# switch_strip.net
KiCad netlist of a schematic drawn in EAGLE
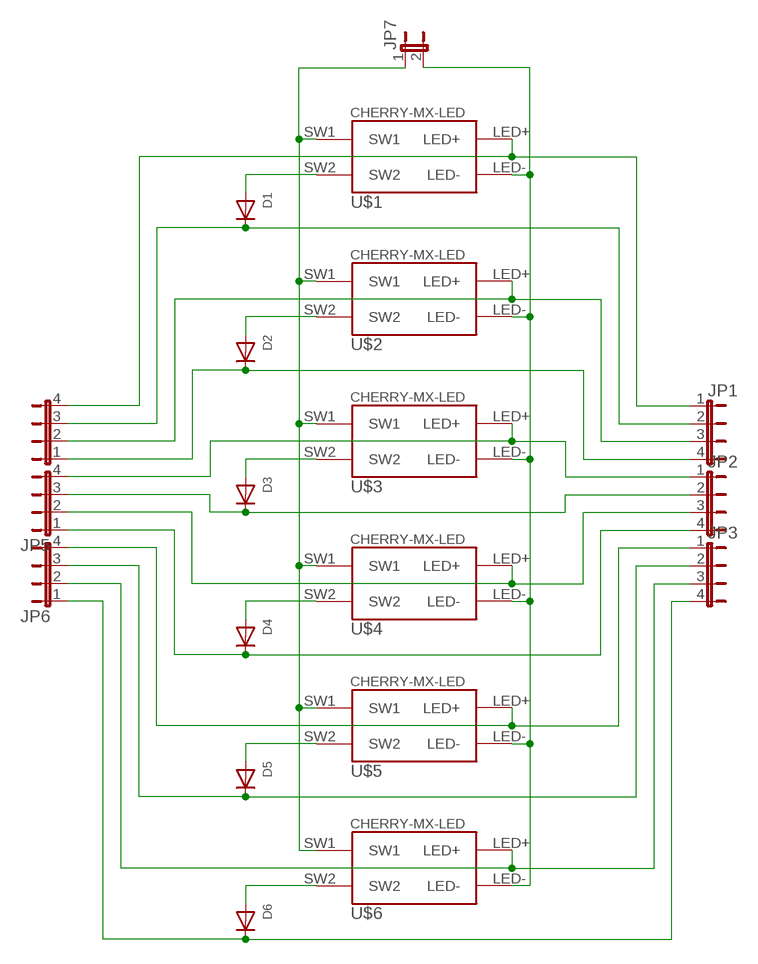
[diagram p0: schematic, sheet 1]

(export (version "E")
  (design (tool "Eeschema 10.0.6"))
  (components
    (comp (ref "D1")
      (value "DIODEDO-1N4148")
      (footprint "eagle-import:DO-1N4148")
      (libsource (lib "eagle-import") (part "DIODEDO-1N4148"))
    )
    (comp (ref "D2")
      (value "DIODEDO-1N4148")
      (footprint "eagle-import:DO-1N4148")
      (libsource (lib "eagle-import") (part "DIODEDO-1N4148"))
    )
    (comp (ref "D3")
      (value "DIODEDO-1N4148")
      (footprint "eagle-import:DO-1N4148")
      (libsource (lib "eagle-import") (part "DIODEDO-1N4148"))
    )
    (comp (ref "D4")
      (value "DIODEDO-1N4148")
      (footprint "eagle-import:DO-1N4148")
      (libsource (lib "eagle-import") (part "DIODEDO-1N4148"))
    )
    (comp (ref "D5")
      (value "DIODEDO-1N4148")
      (footprint "eagle-import:DO-1N4148")
      (libsource (lib "eagle-import") (part "DIODEDO-1N4148"))
    )
    (comp (ref "D6")
      (value "DIODEDO-1N4148")
      (footprint "eagle-import:DO-1N4148")
      (libsource (lib "eagle-import") (part "DIODEDO-1N4148"))
    )
    (comp (ref "JP1")
      (value "JP4E")
      (footprint "eagle-import:JP4")
      (libsource (lib "eagle-import") (part "JP4E"))
    )
    (comp (ref "JP2")
      (value "JP4E")
      (footprint "eagle-import:JP4")
      (libsource (lib "eagle-import") (part "JP4E"))
    )
    (comp (ref "JP3")
      (value "JP4E")
      (footprint "eagle-import:JP4")
      (libsource (lib "eagle-import") (part "JP4E"))
    )
    (comp (ref "JP4")
      (value "JP4E")
      (footprint "eagle-import:JP4")
      (libsource (lib "eagle-import") (part "JP4E"))
    )
    (comp (ref "JP5")
      (value "JP4E")
      (footprint "eagle-import:JP4")
      (libsource (lib "eagle-import") (part "JP4E"))
    )
    (comp (ref "JP6")
      (value "JP4E")
      (footprint "eagle-import:JP4")
      (libsource (lib "eagle-import") (part "JP4E"))
    )
    (comp (ref "JP7")
      (value "JP1E")
      (footprint "eagle-import:JP1")
      (libsource (lib "eagle-import") (part "JP1E"))
    )
    (comp (ref "U$1")
      (value "CHERRY-MX-LED")
      (footprint "eagle-import:CHERRY-MX-LED")
      (libsource (lib "eagle-import") (part "CHERRY-MX-LED"))
    )
    (comp (ref "U$2")
      (value "CHERRY-MX-LED")
      (footprint "eagle-import:CHERRY-MX-LED")
      (libsource (lib "eagle-import") (part "CHERRY-MX-LED"))
    )
    (comp (ref "U$3")
      (value "CHERRY-MX-LED")
      (footprint "eagle-import:CHERRY-MX-LED")
      (libsource (lib "eagle-import") (part "CHERRY-MX-LED"))
    )
    (comp (ref "U$4")
      (value "CHERRY-MX-LED")
      (footprint "eagle-import:CHERRY-MX-LED")
      (libsource (lib "eagle-import") (part "CHERRY-MX-LED"))
    )
    (comp (ref "U$5")
      (value "CHERRY-MX-LED")
      (footprint "eagle-import:CHERRY-MX-LED")
      (libsource (lib "eagle-import") (part "CHERRY-MX-LED"))
    )
    (comp (ref "U$6")
      (value "CHERRY-MX-LED")
      (footprint "eagle-import:CHERRY-MX-LED")
      (libsource (lib "eagle-import") (part "CHERRY-MX-LED"))
    )
  )
  (nets
    (net (code "1") (name "Net-(D1-PadA)") (class "Default")
      (node (ref "D1") (pin "A") (pinfunction "A_A") (pintype "passive"))
      (node (ref "U$1") (pin "SW2") (pinfunction "SW2_SW2") (pintype "bidirectional"))
    )
    (net (code "2") (name "Net-(D1-PadC)") (class "Default")
      (node (ref "D1") (pin "C") (pinfunction "C_C") (pintype "passive"))
      (node (ref "JP1") (pin "2") (pinfunction "2_2") (pintype "passive"))
      (node (ref "JP4") (pin "3") (pinfunction "3_3") (pintype "passive"))
    )
    (net (code "3") (name "Net-(D2-PadA)") (class "Default")
      (node (ref "D2") (pin "A") (pinfunction "A_A") (pintype "passive"))
      (node (ref "U$2") (pin "SW2") (pinfunction "SW2_SW2") (pintype "bidirectional"))
    )
    (net (code "4") (name "Net-(D2-PadC)") (class "Default")
      (node (ref "D2") (pin "C") (pinfunction "C_C") (pintype "passive"))
      (node (ref "JP1") (pin "4") (pinfunction "4_4") (pintype "passive"))
      (node (ref "JP4") (pin "1") (pinfunction "1_1") (pintype "passive"))
    )
    (net (code "5") (name "Net-(D3-PadA)") (class "Default")
      (node (ref "D3") (pin "A") (pinfunction "A_A") (pintype "passive"))
      (node (ref "U$3") (pin "SW2") (pinfunction "SW2_SW2") (pintype "bidirectional"))
    )
    (net (code "6") (name "Net-(D3-PadC)") (class "Default")
      (node (ref "D3") (pin "C") (pinfunction "C_C") (pintype "passive"))
      (node (ref "JP2") (pin "2") (pinfunction "2_2") (pintype "passive"))
      (node (ref "JP5") (pin "3") (pinfunction "3_3") (pintype "passive"))
    )
    (net (code "7") (name "Net-(D4-PadA)") (class "Default")
      (node (ref "D4") (pin "A") (pinfunction "A_A") (pintype "passive"))
      (node (ref "U$4") (pin "SW2") (pinfunction "SW2_SW2") (pintype "bidirectional"))
    )
    (net (code "8") (name "Net-(D4-PadC)") (class "Default")
      (node (ref "D4") (pin "C") (pinfunction "C_C") (pintype "passive"))
      (node (ref "JP2") (pin "4") (pinfunction "4_4") (pintype "passive"))
      (node (ref "JP5") (pin "1") (pinfunction "1_1") (pintype "passive"))
    )
    (net (code "9") (name "Net-(D5-PadA)") (class "Default")
      (node (ref "D5") (pin "A") (pinfunction "A_A") (pintype "passive"))
      (node (ref "U$5") (pin "SW2") (pinfunction "SW2_SW2") (pintype "bidirectional"))
    )
    (net (code "10") (name "Net-(D5-PadC)") (class "Default")
      (node (ref "D5") (pin "C") (pinfunction "C_C") (pintype "passive"))
      (node (ref "JP3") (pin "2") (pinfunction "2_2") (pintype "passive"))
      (node (ref "JP6") (pin "3") (pinfunction "3_3") (pintype "passive"))
    )
    (net (code "11") (name "Net-(D6-PadA)") (class "Default")
      (node (ref "D6") (pin "A") (pinfunction "A_A") (pintype "passive"))
      (node (ref "U$6") (pin "SW2") (pinfunction "SW2_SW2") (pintype "bidirectional"))
    )
    (net (code "12") (name "Net-(D6-PadC)") (class "Default")
      (node (ref "D6") (pin "C") (pinfunction "C_C") (pintype "passive"))
      (node (ref "JP3") (pin "4") (pinfunction "4_4") (pintype "passive"))
      (node (ref "JP6") (pin "1") (pinfunction "1_1") (pintype "passive"))
    )
    (net (code "13") (name "Net-(JP1-Pad1)") (class "Default")
      (node (ref "JP1") (pin "1") (pinfunction "1_1") (pintype "passive"))
      (node (ref "JP4") (pin "4") (pinfunction "4_4") (pintype "passive"))
      (node (ref "U$1") (pin "LED+") (pinfunction "LED+_LED+") (pintype "bidirectional"))
    )
    (net (code "14") (name "Net-(JP1-Pad3)") (class "Default")
      (node (ref "JP1") (pin "3") (pinfunction "3_3") (pintype "passive"))
      (node (ref "JP4") (pin "2") (pinfunction "2_2") (pintype "passive"))
      (node (ref "U$2") (pin "LED+") (pinfunction "LED+_LED+") (pintype "bidirectional"))
    )
    (net (code "15") (name "Net-(JP2-Pad1)") (class "Default")
      (node (ref "JP2") (pin "1") (pinfunction "1_1") (pintype "passive"))
      (node (ref "JP5") (pin "4") (pinfunction "4_4") (pintype "passive"))
      (node (ref "U$3") (pin "LED+") (pinfunction "LED+_LED+") (pintype "bidirectional"))
    )
    (net (code "16") (name "Net-(JP2-Pad3)") (class "Default")
      (node (ref "JP2") (pin "3") (pinfunction "3_3") (pintype "passive"))
      (node (ref "JP5") (pin "2") (pinfunction "2_2") (pintype "passive"))
      (node (ref "U$4") (pin "LED+") (pinfunction "LED+_LED+") (pintype "bidirectional"))
    )
    (net (code "17") (name "Net-(JP3-Pad1)") (class "Default")
      (node (ref "JP3") (pin "1") (pinfunction "1_1") (pintype "passive"))
      (node (ref "JP6") (pin "4") (pinfunction "4_4") (pintype "passive"))
      (node (ref "U$5") (pin "LED+") (pinfunction "LED+_LED+") (pintype "bidirectional"))
    )
    (net (code "18") (name "Net-(JP3-Pad3)") (class "Default")
      (node (ref "JP3") (pin "3") (pinfunction "3_3") (pintype "passive"))
      (node (ref "JP6") (pin "2") (pinfunction "2_2") (pintype "passive"))
      (node (ref "U$6") (pin "LED+") (pinfunction "LED+_LED+") (pintype "bidirectional"))
    )
    (net (code "19") (name "Net-(JP7-Pad1)") (class "Default")
      (node (ref "JP7") (pin "1") (pinfunction "1_1") (pintype "passive"))
      (node (ref "U$1") (pin "SW1") (pinfunction "SW1_SW1") (pintype "bidirectional"))
      (node (ref "U$2") (pin "SW1") (pinfunction "SW1_SW1") (pintype "bidirectional"))
      (node (ref "U$3") (pin "SW1") (pinfunction "SW1_SW1") (pintype "bidirectional"))
      (node (ref "U$4") (pin "SW1") (pinfunction "SW1_SW1") (pintype "bidirectional"))
      (node (ref "U$5") (pin "SW1") (pinfunction "SW1_SW1") (pintype "bidirectional"))
      (node (ref "U$6") (pin "SW1") (pinfunction "SW1_SW1") (pintype "bidirectional"))
    )
    (net (code "20") (name "Net-(JP7-Pad2)") (class "Default")
      (node (ref "JP7") (pin "2") (pinfunction "2_2") (pintype "passive"))
      (node (ref "U$1") (pin "LED-") (pinfunction "LED-_LED-") (pintype "bidirectional"))
      (node (ref "U$2") (pin "LED-") (pinfunction "LED-_LED-") (pintype "bidirectional"))
      (node (ref "U$3") (pin "LED-") (pinfunction "LED-_LED-") (pintype "bidirectional"))
      (node (ref "U$4") (pin "LED-") (pinfunction "LED-_LED-") (pintype "bidirectional"))
      (node (ref "U$5") (pin "LED-") (pinfunction "LED-_LED-") (pintype "bidirectional"))
      (node (ref "U$6") (pin "LED-") (pinfunction "LED-_LED-") (pintype "bidirectional"))
    )
  )
)
